# Esquematico.net
KiCad netlist of a schematic drawn in Altium Designer
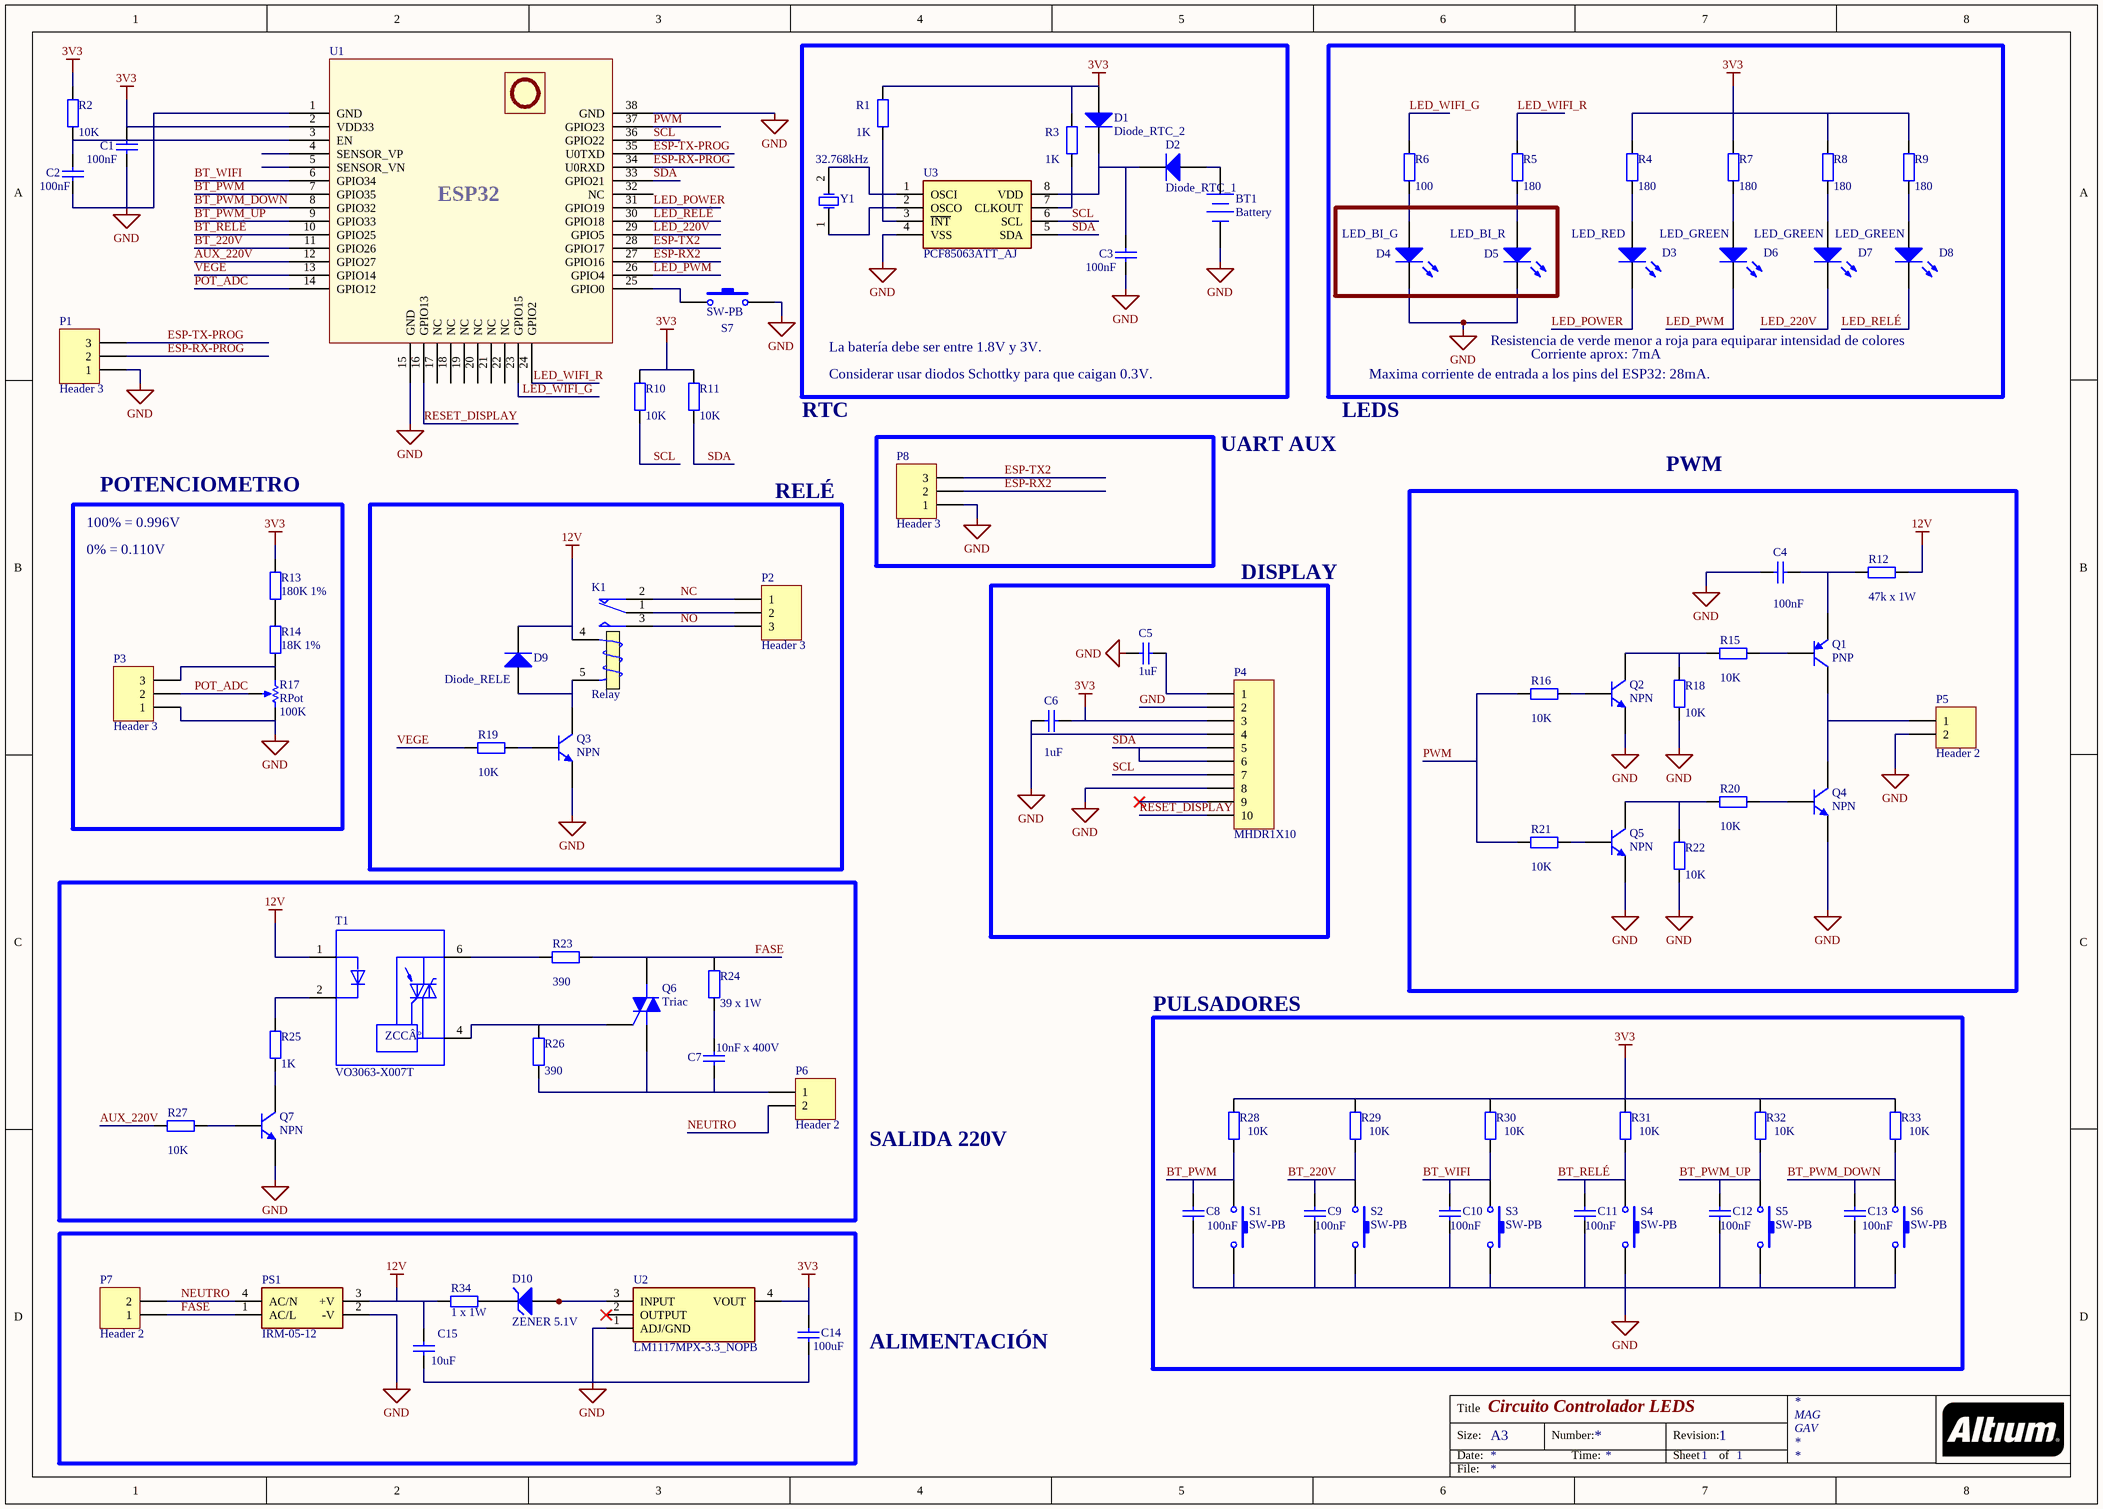
[diagram p0: Esquematico.SchDoc]

(export (version "E")
  (design (tool "Eeschema 10.0.6"))
  (components
    (comp (ref "BT1")
      (value "Battery")
      (footprint "BAT-2")
      (description "Multicell Battery")
      (fields (field (name "PUBLISHER") "Altium Limited"))
      (libsource (lib "Miscellaneous Devices") (part "Battery"))
    )
    (comp (ref "C1")
      (value "100nF")
      (footprint "RAD-0.3")
      (description "Capacitor")
      (fields (field (name "Comment") "Capacitor 100nF") (field (name "PUBLISHER") "Altium Limited"))
      (libsource (lib "Miscellaneous Devices") (part "Cap"))
    )
    (comp (ref "C2")
      (value "100nF")
      (footprint "RAD-0.3")
      (description "Capacitor")
      (fields (field (name "Comment") "Capacitor 100nF") (field (name "PUBLISHER") "Altium Limited"))
      (libsource (lib "Miscellaneous Devices") (part "Cap"))
    )
    (comp (ref "C3")
      (value "100nF")
      (footprint "RAD-0.3")
      (description "Capacitor")
      (fields (field (name "Comment") "Capacitor 100nF") (field (name "PUBLISHER") "Altium Limited"))
      (libsource (lib "Miscellaneous Devices") (part "Cap"))
    )
    (comp (ref "C4")
      (value "100nF")
      (footprint "RAD-0.3")
      (description "Capacitor")
      (fields (field (name "Comment") "Capacitor 100nF") (field (name "PUBLISHER") "Altium Limited"))
      (libsource (lib "Miscellaneous Devices") (part "Cap"))
    )
    (comp (ref "C5")
      (value "1uF")
      (footprint "RAD-0.3")
      (description "Capacitor")
      (fields (field (name "Comment") "Capacitor 1uF") (field (name "PUBLISHER") "Altium Limited"))
      (libsource (lib "Miscellaneous Devices") (part "Cap"))
    )
    (comp (ref "C6")
      (value "1uF")
      (footprint "RAD-0.3")
      (description "Capacitor")
      (fields (field (name "Comment") "Capacitor 1uF") (field (name "PUBLISHER") "Altium Limited"))
      (libsource (lib "Miscellaneous Devices") (part "Cap"))
    )
    (comp (ref "C7")
      (value "10nF x 400V")
      (footprint "RAD-0.3")
      (description "Capacitor")
      (fields (field (name "Comment") "Capacitor 10nF") (field (name "PUBLISHER") "Altium Limited"))
      (libsource (lib "Miscellaneous Devices") (part "Cap"))
    )
    (comp (ref "C8")
      (value "100nF")
      (footprint "RAD-0.3")
      (description "Capacitor")
      (fields (field (name "Comment") "Capacitor 100nF") (field (name "PUBLISHER") "Altium Limited"))
      (libsource (lib "Miscellaneous Devices") (part "Cap"))
    )
    (comp (ref "C9")
      (value "100nF")
      (footprint "RAD-0.3")
      (description "Capacitor")
      (fields (field (name "Comment") "Capacitor 100nF") (field (name "PUBLISHER") "Altium Limited"))
      (libsource (lib "Miscellaneous Devices") (part "Cap"))
    )
    (comp (ref "C10")
      (value "100nF")
      (footprint "RAD-0.3")
      (description "Capacitor")
      (fields (field (name "Comment") "Capacitor 100nF") (field (name "PUBLISHER") "Altium Limited"))
      (libsource (lib "Miscellaneous Devices") (part "Cap"))
    )
    (comp (ref "C11")
      (value "100nF")
      (footprint "RAD-0.3")
      (description "Capacitor")
      (fields (field (name "Comment") "Capacitor 100nF") (field (name "PUBLISHER") "Altium Limited"))
      (libsource (lib "Miscellaneous Devices") (part "Cap"))
    )
    (comp (ref "C12")
      (value "100nF")
      (footprint "RAD-0.3")
      (description "Capacitor")
      (fields (field (name "Comment") "Capacitor 100nF") (field (name "PUBLISHER") "Altium Limited"))
      (libsource (lib "Miscellaneous Devices") (part "Cap"))
    )
    (comp (ref "C13")
      (value "100nF")
      (footprint "RAD-0.3")
      (description "Capacitor")
      (fields (field (name "Comment") "Capacitor 100nF") (field (name "PUBLISHER") "Altium Limited"))
      (libsource (lib "Miscellaneous Devices") (part "Cap"))
    )
    (comp (ref "C14")
      (value "100uF")
      (footprint "RAD-0.3")
      (description "Capacitor")
      (fields (field (name "Comment") "Capacitor 100uF") (field (name "PUBLISHER") "Altium Limited"))
      (libsource (lib "Miscellaneous Devices") (part "Cap"))
    )
    (comp (ref "C15")
      (value "10uF")
      (footprint "RAD-0.3")
      (description "Capacitor")
      (fields (field (name "Comment") "Capacitor 10uF") (field (name "PUBLISHER") "Altium Limited"))
      (libsource (lib "Miscellaneous Devices") (part "Cap"))
    )
    (comp (ref "D1")
      (value "Diode_RTC_2")
      (footprint "SMC")
      (description "Default Diode")
      (fields (field (name "PUBLISHER") "Altium Limited"))
      (libsource (lib "Miscellaneous Devices") (part "Diode"))
    )
    (comp (ref "D2")
      (value "Diode_RTC_1")
      (footprint "SMC")
      (description "Default Diode")
      (fields (field (name "PUBLISHER") "Altium Limited"))
      (libsource (lib "Miscellaneous Devices") (part "Diode"))
    )
    (comp (ref "D3")
      (value "LED_RED")
      (footprint "LED-0")
      (description "Typical INFRARED GaAs LED")
      (fields (field (name "PUBLISHER") "Altium Limited"))
      (libsource (lib "Miscellaneous Devices") (part "LED0"))
    )
    (comp (ref "D4")
      (value "LED_BI_G")
      (footprint "LED-0")
      (description "Typical INFRARED GaAs LED")
      (fields (field (name "PUBLISHER") "Altium Limited"))
      (libsource (lib "Miscellaneous Devices") (part "LED0"))
    )
    (comp (ref "D5")
      (value "LED_BI_R")
      (footprint "LED-0")
      (description "Typical INFRARED GaAs LED")
      (fields (field (name "PUBLISHER") "Altium Limited"))
      (libsource (lib "Miscellaneous Devices") (part "LED0"))
    )
    (comp (ref "D6")
      (value "LED_GREEN")
      (footprint "LED-0")
      (description "Typical INFRARED GaAs LED")
      (fields (field (name "PUBLISHER") "Altium Limited"))
      (libsource (lib "Miscellaneous Devices") (part "LED0"))
    )
    (comp (ref "D7")
      (value "LED_GREEN")
      (footprint "LED-0")
      (description "Typical INFRARED GaAs LED")
      (fields (field (name "PUBLISHER") "Altium Limited"))
      (libsource (lib "Miscellaneous Devices") (part "LED0"))
    )
    (comp (ref "D8")
      (value "LED_GREEN")
      (footprint "LED-0")
      (description "Typical INFRARED GaAs LED")
      (fields (field (name "PUBLISHER") "Altium Limited"))
      (libsource (lib "Miscellaneous Devices") (part "LED0"))
    )
    (comp (ref "D9")
      (value "Diode_RELE")
      (footprint "SMC")
      (description "Default Diode")
      (fields (field (name "PUBLISHER") "Altium Limited"))
      (libsource (lib "Miscellaneous Devices") (part "Diode"))
    )
    (comp (ref "D10")
      (value "ZENER 5.1V")
      (footprint "DIODE-0.7")
      (description "Zener Diode")
      (fields (field (name "PUBLISHER") "Altium Limited"))
      (libsource (lib "Miscellaneous Devices") (part "D Zener"))
    )
    (comp (ref "K1")
      (value "Relay")
      (footprint "MODULE5B")
      (description "SPDT Relay")
      (fields (field (name "PUBLISHER") "Altium Limited"))
      (libsource (lib "Miscellaneous Devices") (part "Relay"))
    )
    (comp (ref "P1")
      (value "Header 3")
      (footprint "HDR1X3")
      (description "Header, 3-Pin")
      (fields (field (name "PUBLISHER") "Altium Limited"))
      (libsource (lib "Miscellaneous Connectors") (part "Header 3"))
    )
    (comp (ref "P2")
      (value "Header 3")
      (footprint "HDR1X3")
      (description "Header, 3-Pin")
      (fields (field (name "PUBLISHER") "Altium Limited"))
      (libsource (lib "") (part "Header 3_1"))
    )
    (comp (ref "P3")
      (value "Header 3")
      (footprint "HDR1X3")
      (description "Header, 3-Pin")
      (fields (field (name "PUBLISHER") "Altium Limited"))
      (libsource (lib "Miscellaneous Connectors") (part "Header 3"))
    )
    (comp (ref "P4")
      (value "MHDR1X10")
      (footprint "MHDR1X10")
      (description "Header, 10-Pin")
      (fields (field (name "PUBLISHER") "Altium Limited"))
      (libsource (lib "Miscellaneous Connectors") (part "MHDR1X10"))
    )
    (comp (ref "P5")
      (value "Header 2")
      (footprint "HDR1X2")
      (description "Header, 2-Pin")
      (fields (field (name "PUBLISHER") "Altium Limited"))
      (libsource (lib "Miscellaneous Connectors") (part "Header 2"))
    )
    (comp (ref "P6")
      (value "Header 2")
      (footprint "HDR1X2")
      (description "Header, 2-Pin")
      (fields (field (name "PUBLISHER") "Altium Limited"))
      (libsource (lib "Miscellaneous Connectors") (part "Header 2"))
    )
    (comp (ref "P7")
      (value "Header 2")
      (footprint "HDR1X2")
      (description "Header, 2-Pin")
      (fields (field (name "PUBLISHER") "Altium Limited"))
      (libsource (lib "") (part "Header 2_1"))
    )
    (comp (ref "P8")
      (value "Header 3")
      (footprint "HDR1X3")
      (description "Header, 3-Pin")
      (fields (field (name "PUBLISHER") "Altium Limited"))
      (libsource (lib "Miscellaneous Connectors") (part "Header 3"))
    )
    (comp (ref "PS1")
      (value "IRM-05-12")
      (footprint "SamacSys:IRM0524")
      (description "Power Supply")
      (fields
        (field (name "MANUFACTURER_PART_NUMBER") "IRM-05-24")
        (field (name "MOUSER PART NUMBER") "709-IRM05-24")
      )
      (libsource (lib "*") (part "IRM-05-24"))
    )
    (comp (ref "Q1")
      (value "PNP")
      (footprint "SOT-23B_L")
      (description "PNP Bipolar Transistor")
      (fields (field (name "PUBLISHER") "Altium Limited"))
      (libsource (lib "Miscellaneous Devices") (part "PNP"))
    )
    (comp (ref "Q2")
      (value "NPN")
      (footprint "TO-226-AA")
      (description "NPN Bipolar Transistor")
      (fields (field (name "PUBLISHER") "Altium Limited"))
      (libsource (lib "Miscellaneous Devices") (part "NPN"))
    )
    (comp (ref "Q3")
      (value "NPN")
      (footprint "TO-226-AA")
      (description "NPN Bipolar Transistor")
      (fields (field (name "PUBLISHER") "Altium Limited"))
      (libsource (lib "Miscellaneous Devices") (part "NPN"))
    )
    (comp (ref "Q4")
      (value "NPN")
      (footprint "TO-226-AA")
      (description "NPN Bipolar Transistor")
      (fields (field (name "PUBLISHER") "Altium Limited"))
      (libsource (lib "Miscellaneous Devices") (part "NPN"))
    )
    (comp (ref "Q5")
      (value "NPN")
      (footprint "TO-226-AA")
      (description "NPN Bipolar Transistor")
      (fields (field (name "PUBLISHER") "Altium Limited"))
      (libsource (lib "Miscellaneous Devices") (part "NPN"))
    )
    (comp (ref "Q6")
      (value "Triac")
      (footprint "369-03")
      (description "Silicon Bidirectional Triode Thyristor")
      (fields (field (name "PUBLISHER") "Altium Limited"))
      (libsource (lib "Miscellaneous Devices") (part "Triac"))
    )
    (comp (ref "Q7")
      (value "NPN")
      (footprint "TO-226-AA")
      (description "NPN Bipolar Transistor")
      (fields (field (name "PUBLISHER") "Altium Limited"))
      (libsource (lib "Miscellaneous Devices") (part "NPN"))
    )
    (comp (ref "R1")
      (value "1K")
      (footprint "AXIAL-0.4")
      (description "Resistor")
      (fields (field (name "Comment") "Resistor 1k") (field (name "PUBLISHER") "Altium Limited"))
      (libsource (lib "") (part "Res2_1"))
    )
    (comp (ref "R2")
      (value "10K")
      (footprint "AXIAL-0.4")
      (description "Resistor")
      (fields (field (name "Comment") "Resistor 10k") (field (name "PUBLISHER") "Altium Limited"))
      (libsource (lib "Miscellaneous Devices") (part "Res2"))
    )
    (comp (ref "R3")
      (value "1K")
      (footprint "AXIAL-0.4")
      (description "Resistor")
      (fields (field (name "Comment") "Resistor 1k") (field (name "PUBLISHER") "Altium Limited"))
      (libsource (lib "") (part "Res2_1"))
    )
    (comp (ref "R4")
      (value "180")
      (footprint "AXIAL-0.4")
      (description "Resistor")
      (fields (field (name "Comment") "Resistor 100") (field (name "PUBLISHER") "Altium Limited"))
      (libsource (lib "") (part "Res2_1"))
    )
    (comp (ref "R5")
      (value "180")
      (footprint "AXIAL-0.4")
      (description "Resistor")
      (fields (field (name "Comment") "Resistor 50") (field (name "PUBLISHER") "Altium Limited"))
      (libsource (lib "") (part "Res2_1"))
    )
    (comp (ref "R6")
      (value "100")
      (footprint "AXIAL-0.4")
      (description "Resistor")
      (fields (field (name "Comment") "Resistor 100") (field (name "PUBLISHER") "Altium Limited"))
      (libsource (lib "") (part "Res2_1"))
    )
    (comp (ref "R7")
      (value "180")
      (footprint "AXIAL-0.4")
      (description "Resistor")
      (fields (field (name "Comment") "Resistor 100") (field (name "PUBLISHER") "Altium Limited"))
      (libsource (lib "") (part "Res2_1"))
    )
    (comp (ref "R8")
      (value "180")
      (footprint "AXIAL-0.4")
      (description "Resistor")
      (fields (field (name "Comment") "Resistor 100") (field (name "PUBLISHER") "Altium Limited"))
      (libsource (lib "") (part "Res2_1"))
    )
    (comp (ref "R9")
      (value "180")
      (footprint "AXIAL-0.4")
      (description "Resistor")
      (fields (field (name "Comment") "Resistor 100") (field (name "PUBLISHER") "Altium Limited"))
      (libsource (lib "") (part "Res2_1"))
    )
    (comp (ref "R10")
      (value "10K")
      (footprint "AXIAL-0.4")
      (description "Resistor")
      (fields (field (name "Comment") "Resistor 10k") (field (name "PUBLISHER") "Altium Limited"))
      (libsource (lib "Miscellaneous Devices") (part "Res2"))
    )
    (comp (ref "R11")
      (value "10K")
      (footprint "AXIAL-0.4")
      (description "Resistor")
      (fields (field (name "Comment") "Resistor 10k") (field (name "PUBLISHER") "Altium Limited"))
      (libsource (lib "Miscellaneous Devices") (part "Res2"))
    )
    (comp (ref "R12")
      (value "47k x 1W")
      (footprint "AXIAL-0.4")
      (description "Resistor")
      (fields (field (name "Comment") "Resistor 47k") (field (name "PUBLISHER") "Altium Limited"))
      (libsource (lib "") (part "Res2_2"))
    )
    (comp (ref "R13")
      (value "180K 1%")
      (footprint "AXIAL-0.4")
      (description "Resistor")
      (fields (field (name "Comment") "Resistor 180k") (field (name "PUBLISHER") "Altium Limited"))
      (libsource (lib "Miscellaneous Devices") (part "Res2"))
    )
    (comp (ref "R14")
      (value "18K 1%")
      (footprint "AXIAL-0.4")
      (description "Resistor")
      (fields (field (name "Comment") "Resistor 18k 1%") (field (name "PUBLISHER") "Altium Limited"))
      (libsource (lib "Miscellaneous Devices") (part "Res2"))
    )
    (comp (ref "R15")
      (value "10K")
      (footprint "AXIAL-0.4")
      (description "Resistor")
      (fields (field (name "Comment") "Resistor 10k") (field (name "PUBLISHER") "Altium Limited"))
      (libsource (lib "") (part "Res2_2"))
    )
    (comp (ref "R16")
      (value "10K")
      (footprint "AXIAL-0.4")
      (description "Resistor")
      (fields (field (name "Comment") "Resistor 10k") (field (name "PUBLISHER") "Altium Limited"))
      (libsource (lib "") (part "Res2_2"))
    )
    (comp (ref "R17")
      (value "RPot")
      (footprint "VR5")
      (description "Potentiometer")
      (fields (field (name "ALTIUM_VALUE") "100K") (field (name "PUBLISHER") "Altium Limited"))
      (libsource (lib "Miscellaneous Devices") (part "RPot"))
    )
    (comp (ref "R18")
      (value "10K")
      (footprint "AXIAL-0.4")
      (description "Resistor")
      (fields (field (name "Comment") "Resistor 10k") (field (name "PUBLISHER") "Altium Limited"))
      (libsource (lib "") (part "Res2_1"))
    )
    (comp (ref "R19")
      (value "10K")
      (footprint "AXIAL-0.4")
      (description "Resistor")
      (fields (field (name "Comment") "Resistor 10k") (field (name "PUBLISHER") "Altium Limited"))
      (libsource (lib "") (part "Res2_3"))
    )
    (comp (ref "R20")
      (value "10K")
      (footprint "AXIAL-0.4")
      (description "Resistor")
      (fields (field (name "Comment") "Resistor 10k") (field (name "PUBLISHER") "Altium Limited"))
      (libsource (lib "") (part "Res2_2"))
    )
    (comp (ref "R21")
      (value "10K")
      (footprint "AXIAL-0.4")
      (description "Resistor")
      (fields (field (name "Comment") "Resistor 10k") (field (name "PUBLISHER") "Altium Limited"))
      (libsource (lib "") (part "Res2_2"))
    )
    (comp (ref "R22")
      (value "10K")
      (footprint "AXIAL-0.4")
      (description "Resistor")
      (fields (field (name "Comment") "Resistor 10k") (field (name "PUBLISHER") "Altium Limited"))
      (libsource (lib "") (part "Res2_1"))
    )
    (comp (ref "R23")
      (value "390")
      (footprint "AXIAL-0.4")
      (description "Resistor")
      (fields (field (name "Comment") "Resistor 390") (field (name "PUBLISHER") "Altium Limited"))
      (libsource (lib "") (part "Res2_3"))
    )
    (comp (ref "R24")
      (value "39 x 1W")
      (footprint "AXIAL-0.4")
      (description "Resistor")
      (fields (field (name "Comment") "Resistor 39") (field (name "PUBLISHER") "Altium Limited"))
      (libsource (lib "") (part "Res2_1"))
    )
    (comp (ref "R25")
      (value "1K")
      (footprint "AXIAL-0.4")
      (description "Resistor")
      (fields (field (name "Comment") "Resistor 1k") (field (name "PUBLISHER") "Altium Limited"))
      (libsource (lib "") (part "Res2_1"))
    )
    (comp (ref "R26")
      (value "390")
      (footprint "AXIAL-0.4")
      (description "Resistor")
      (fields (field (name "Comment") "Resistor 390") (field (name "PUBLISHER") "Altium Limited"))
      (libsource (lib "Miscellaneous Devices") (part "Res2"))
    )
    (comp (ref "R27")
      (value "10K")
      (footprint "AXIAL-0.4")
      (description "Resistor")
      (fields (field (name "Comment") "Resistor 10k") (field (name "PUBLISHER") "Altium Limited"))
      (libsource (lib "") (part "Res2_3"))
    )
    (comp (ref "R28")
      (value "10K")
      (footprint "AXIAL-0.4")
      (description "Resistor")
      (fields (field (name "Comment") "Resistor 10k") (field (name "PUBLISHER") "Altium Limited"))
      (libsource (lib "") (part "Res2_1"))
    )
    (comp (ref "R29")
      (value "10K")
      (footprint "AXIAL-0.4")
      (description "Resistor")
      (fields (field (name "Comment") "Resistor 10k") (field (name "PUBLISHER") "Altium Limited"))
      (libsource (lib "") (part "Res2_1"))
    )
    (comp (ref "R30")
      (value "10K")
      (footprint "AXIAL-0.4")
      (description "Resistor")
      (fields (field (name "Comment") "Resistor 10k") (field (name "PUBLISHER") "Altium Limited"))
      (libsource (lib "") (part "Res2_1"))
    )
    (comp (ref "R31")
      (value "10K")
      (footprint "AXIAL-0.4")
      (description "Resistor")
      (fields (field (name "Comment") "Resistor 10k") (field (name "PUBLISHER") "Altium Limited"))
      (libsource (lib "") (part "Res2_1"))
    )
    (comp (ref "R32")
      (value "10K")
      (footprint "AXIAL-0.4")
      (description "Resistor")
      (fields (field (name "Comment") "Resistor 10k") (field (name "PUBLISHER") "Altium Limited"))
      (libsource (lib "") (part "Res2_1"))
    )
    (comp (ref "R33")
      (value "10K")
      (footprint "AXIAL-0.4")
      (description "Resistor")
      (fields (field (name "Comment") "Resistor 10k") (field (name "PUBLISHER") "Altium Limited"))
      (libsource (lib "") (part "Res2_1"))
    )
    (comp (ref "R34")
      (value "1 x 1W")
      (footprint "AXIAL-0.4")
      (description "Resistor")
      (fields (field (name "Comment") "Resistor 1") (field (name "PUBLISHER") "Altium Limited"))
      (libsource (lib "") (part "Res2_2"))
    )
    (comp (ref "S1")
      (value "SW-PB")
      (footprint "SPST-2")
      (description "Switch")
      (fields (field (name "PUBLISHER") "Altium Limited"))
      (libsource (lib "Miscellaneous Devices") (part "SW-PB"))
    )
    (comp (ref "S2")
      (value "SW-PB")
      (footprint "SPST-2")
      (description "Switch")
      (fields (field (name "PUBLISHER") "Altium Limited"))
      (libsource (lib "Miscellaneous Devices") (part "SW-PB"))
    )
    (comp (ref "S3")
      (value "SW-PB")
      (footprint "SPST-2")
      (description "Switch")
      (fields (field (name "PUBLISHER") "Altium Limited"))
      (libsource (lib "Miscellaneous Devices") (part "SW-PB"))
    )
    (comp (ref "S4")
      (value "SW-PB")
      (footprint "SPST-2")
      (description "Switch")
      (fields (field (name "PUBLISHER") "Altium Limited"))
      (libsource (lib "Miscellaneous Devices") (part "SW-PB"))
    )
    (comp (ref "S5")
      (value "SW-PB")
      (footprint "SPST-2")
      (description "Switch")
      (fields (field (name "PUBLISHER") "Altium Limited"))
      (libsource (lib "Miscellaneous Devices") (part "SW-PB"))
    )
    (comp (ref "S6")
      (value "SW-PB")
      (footprint "SPST-2")
      (description "Switch")
      (fields (field (name "PUBLISHER") "Altium Limited"))
      (libsource (lib "Miscellaneous Devices") (part "SW-PB"))
    )
    (comp (ref "S7")
      (value "SW-PB")
      (footprint "SPST-2")
      (description "Switch")
      (fields (field (name "PUBLISHER") "Altium Limited"))
      (libsource (lib "Miscellaneous Devices") (part "SW-PB"))
    )
    (comp (ref "T1")
      (value "VO3063-X007T")
      (footprint "SOIC254P1030X460-6N")
      (description "Phototriac, Zero Crossing, 1.5 kV/渭s dV/dt, 600 V")
      (libsource (lib "VO3063-X007T") (part "VO3063-X007T"))
    )
    (comp (ref "U1") (value "ESP32-WROOM-UE32") (libsource (lib "ESP32-WROOM-32UE") (part "Component_1")))
    (comp (ref "U2")
      (value "LM1117MPX-3.3_NOPB")
      (footprint "SamacSys:SOT230P700X180-4N")
      (description "Integrated Circuit")
      (fields
        (field (name "MANUFACTURER_PART_NUMBER") "LM1117MPX-3.3/NOPB")
        (field (name "MOUSER PART NUMBER") "926-LM1117MPX3.3NOPB")
      )
      (libsource (lib "SamacSys") (part "LM1117MPX-3.3_NOPB"))
    )
    (comp (ref "U3")
      (value "PCF85063ATT_AJ")
      (footprint "SamacSys:SOP65P490X110-8N")
      (description "Integrated Circuit")
      (fields
        (field (name "MANUFACTURER_PART_NUMBER") "PCF85063ATT/AJ")
        (field (name "MOUSER PART NUMBER") "771-PCF85063ATT/AJ")
      )
      (libsource (lib "*") (part "PCF85063ATT_AJ"))
    )
    (comp (ref "Y1")
      (value "32.768kHz")
      (footprint "R38")
      (description "Crystal Oscillator")
      (fields (field (name "PUBLISHER") "Altium Limited"))
      (libsource (lib "Miscellaneous Devices") (part "XTAL"))
    )
  )
  (nets
    (net (code "1") (name "/AUX_220V") (class "Default")
      (node (ref "R27") (pin "2") (pinfunction "2_2") (pintype "passive"))
      (node (ref "U1") (pin "12") (pinfunction "GPIO27_12") (pintype "passive"))
    )
    (net (code "2") (name "/BT_220V") (class "Default")
      (node (ref "C9") (pin "2") (pinfunction "2_2") (pintype "passive"))
      (node (ref "R29") (pin "1") (pinfunction "1_1") (pintype "passive"))
      (node (ref "S2") (pin "1") (pinfunction "1_1") (pintype "passive"))
      (node (ref "U1") (pin "11") (pinfunction "GPIO26_11") (pintype "passive"))
    )
    (net (code "3") (name "/BT_PWM") (class "Default")
      (node (ref "C8") (pin "2") (pinfunction "2_2") (pintype "passive"))
      (node (ref "R28") (pin "1") (pinfunction "1_1") (pintype "passive"))
      (node (ref "S1") (pin "1") (pinfunction "1_1") (pintype "passive"))
      (node (ref "U1") (pin "7") (pinfunction "GPIO35_7") (pintype "passive"))
    )
    (net (code "4") (name "/BT_PWM_DOWN") (class "Default")
      (node (ref "C13") (pin "2") (pinfunction "2_2") (pintype "passive"))
      (node (ref "R33") (pin "1") (pinfunction "1_1") (pintype "passive"))
      (node (ref "S6") (pin "1") (pinfunction "1_1") (pintype "passive"))
      (node (ref "U1") (pin "8") (pinfunction "GPIO32_8") (pintype "passive"))
    )
    (net (code "5") (name "/BT_PWM_UP") (class "Default")
      (node (ref "C12") (pin "2") (pinfunction "2_2") (pintype "passive"))
      (node (ref "R32") (pin "1") (pinfunction "1_1") (pintype "passive"))
      (node (ref "S5") (pin "1") (pinfunction "1_1") (pintype "passive"))
      (node (ref "U1") (pin "9") (pinfunction "GPIO33_9") (pintype "passive"))
    )
    (net (code "6") (name "/BT_RELÉ") (class "Default")
      (node (ref "C11") (pin "2") (pinfunction "2_2") (pintype "passive"))
      (node (ref "R31") (pin "1") (pinfunction "1_1") (pintype "passive"))
      (node (ref "S4") (pin "1") (pinfunction "1_1") (pintype "passive"))
      (node (ref "U1") (pin "10") (pinfunction "GPIO25_10") (pintype "passive"))
    )
    (net (code "7") (name "/BT_WIFI") (class "Default")
      (node (ref "C10") (pin "2") (pinfunction "2_2") (pintype "passive"))
      (node (ref "R30") (pin "1") (pinfunction "1_1") (pintype "passive"))
      (node (ref "S3") (pin "1") (pinfunction "1_1") (pintype "passive"))
      (node (ref "U1") (pin "6") (pinfunction "GPIO34_6") (pintype "passive"))
    )
    (net (code "8") (name "/ESP-RX-PROG") (class "Default")
      (node (ref "P1") (pin "2") (pinfunction "2_2") (pintype "passive"))
      (node (ref "U1") (pin "34") (pinfunction "U0RXD_34") (pintype "passive"))
    )
    (net (code "9") (name "/ESP-RX2") (class "Default")
      (node (ref "P8") (pin "2") (pinfunction "2_2") (pintype "passive"))
      (node (ref "U1") (pin "27") (pinfunction "GPIO16_27") (pintype "passive"))
    )
    (net (code "10") (name "/ESP-TX-PROG") (class "Default")
      (node (ref "P1") (pin "3") (pinfunction "3_3") (pintype "passive"))
      (node (ref "U1") (pin "35") (pinfunction "U0TXD_35") (pintype "passive"))
    )
    (net (code "11") (name "/ESP-TX2") (class "Default")
      (node (ref "P8") (pin "3") (pinfunction "3_3") (pintype "passive"))
      (node (ref "U1") (pin "28") (pinfunction "GPIO17_28") (pintype "passive"))
    )
    (net (code "12") (name "/FASE") (class "Default")
      (node (ref "P7") (pin "1") (pinfunction "1_1") (pintype "passive"))
      (node (ref "PS1") (pin "1") (pinfunction "AC/L_1") (pintype "passive"))
      (node (ref "Q6") (pin "2") (pinfunction "M2_2") (pintype "passive"))
      (node (ref "R23") (pin "1") (pinfunction "1_1") (pintype "passive"))
      (node (ref "R24") (pin "2") (pinfunction "2_2") (pintype "passive"))
    )
    (net (code "13") (name "/LED_220V") (class "Default")
      (node (ref "D7") (pin "2") (pinfunction "K_2") (pintype "passive"))
      (node (ref "U1") (pin "29") (pinfunction "GPIO5_29") (pintype "passive"))
    )
    (net (code "14") (name "/LED_POWER") (class "Default")
      (node (ref "D3") (pin "2") (pinfunction "K_2") (pintype "passive"))
      (node (ref "U1") (pin "31") (pinfunction "GPIO19_31") (pintype "passive"))
    )
    (net (code "15") (name "/LED_PWM") (class "Default")
      (node (ref "D6") (pin "2") (pinfunction "K_2") (pintype "passive"))
      (node (ref "U1") (pin "26") (pinfunction "GPIO4_26") (pintype "passive"))
    )
    (net (code "16") (name "/LED_RELÉ") (class "Default")
      (node (ref "D8") (pin "2") (pinfunction "K_2") (pintype "passive"))
      (node (ref "U1") (pin "30") (pinfunction "GPIO18_30") (pintype "passive"))
    )
    (net (code "17") (name "/LED_WIFI_G") (class "Default")
      (node (ref "R6") (pin "2") (pinfunction "2_2") (pintype "passive"))
      (node (ref "U1") (pin "23") (pinfunction "GPIO15_23") (pintype "passive"))
    )
    (net (code "18") (name "/LED_WIFI_R") (class "Default")
      (node (ref "R5") (pin "2") (pinfunction "2_2") (pintype "passive"))
      (node (ref "U1") (pin "24") (pinfunction "GPIO2_24") (pintype "passive"))
    )
    (net (code "19") (name "/NC") (class "Default")
      (node (ref "K1") (pin "2") (pinfunction "NC_2") (pintype "passive"))
      (node (ref "P2") (pin "1") (pinfunction "1_1") (pintype "passive"))
    )
    (net (code "20") (name "/NEUTRO") (class "Default")
      (node (ref "P6") (pin "2") (pinfunction "2_2") (pintype "passive"))
      (node (ref "P7") (pin "2") (pinfunction "2_2") (pintype "passive"))
      (node (ref "PS1") (pin "4") (pinfunction "AC/N_4") (pintype "passive"))
    )
    (net (code "21") (name "/NO") (class "Default")
      (node (ref "K1") (pin "3") (pinfunction "NO_3") (pintype "passive"))
      (node (ref "P2") (pin "3") (pinfunction "3_3") (pintype "passive"))
    )
    (net (code "22") (name "/POT_ADC") (class "Default")
      (node (ref "P3") (pin "2") (pinfunction "2_2") (pintype "passive"))
      (node (ref "R17") (pin "3") (pinfunction "TAP_3") (pintype "passive"))
      (node (ref "U1") (pin "14") (pinfunction "GPIO12_14") (pintype "passive"))
    )
    (net (code "23") (name "/PWM") (class "Default")
      (node (ref "R16") (pin "1") (pinfunction "1_1") (pintype "passive"))
      (node (ref "R21") (pin "1") (pinfunction "1_1") (pintype "passive"))
      (node (ref "U1") (pin "37") (pinfunction "GPIO23_37") (pintype "passive"))
    )
    (net (code "24") (name "/RESET_DISPLAY") (class "Default")
      (node (ref "P4") (pin "10") (pinfunction "10_10") (pintype "passive"))
      (node (ref "U1") (pin "16") (pinfunction "GPIO13_16") (pintype "passive"))
    )
    (net (code "25") (name "/SCL") (class "Default")
      (node (ref "P4") (pin "7") (pinfunction "7_7") (pintype "passive"))
      (node (ref "R10") (pin "2") (pinfunction "2_2") (pintype "passive"))
      (node (ref "U1") (pin "36") (pinfunction "GPIO22_36") (pintype "passive"))
      (node (ref "U3") (pin "6") (pinfunction "SCL_6") (pintype "passive"))
    )
    (net (code "26") (name "/SDA") (class "Default")
      (node (ref "P4") (pin "5") (pinfunction "5_5") (pintype "passive"))
      (node (ref "P4") (pin "6") (pinfunction "6_6") (pintype "passive"))
      (node (ref "R11") (pin "2") (pinfunction "2_2") (pintype "passive"))
      (node (ref "U1") (pin "33") (pinfunction "GPIO21_33") (pintype "passive"))
      (node (ref "U3") (pin "5") (pinfunction "SDA_5") (pintype "passive"))
    )
    (net (code "27") (name "/VEGE") (class "Default")
      (node (ref "R19") (pin "2") (pinfunction "2_2") (pintype "passive"))
      (node (ref "U1") (pin "13") (pinfunction "GPIO14_13") (pintype "passive"))
    )
    (net (code "28") (name "3V3") (class "Default")
      (node (ref "C1") (pin "2") (pinfunction "2_2") (pintype "passive"))
      (node (ref "C14") (pin "2") (pinfunction "2_2") (pintype "passive"))
      (node (ref "C6") (pin "1") (pinfunction "1_1") (pintype "passive"))
      (node (ref "D1") (pin "1") (pinfunction "A_1") (pintype "passive"))
      (node (ref "P4") (pin "3") (pinfunction "3_3") (pintype "passive"))
      (node (ref "R1") (pin "2") (pinfunction "2_2") (pintype "passive"))
      (node (ref "R10") (pin "1") (pinfunction "1_1") (pintype "passive"))
      (node (ref "R11") (pin "1") (pinfunction "1_1") (pintype "passive"))
      (node (ref "R13") (pin "1") (pinfunction "1_1") (pintype "passive"))
      (node (ref "R2") (pin "1") (pinfunction "1_1") (pintype "passive"))
      (node (ref "R28") (pin "2") (pinfunction "2_2") (pintype "passive"))
      (node (ref "R29") (pin "2") (pinfunction "2_2") (pintype "passive"))
      (node (ref "R3") (pin "2") (pinfunction "2_2") (pintype "passive"))
      (node (ref "R30") (pin "2") (pinfunction "2_2") (pintype "passive"))
      (node (ref "R31") (pin "2") (pinfunction "2_2") (pintype "passive"))
      (node (ref "R32") (pin "2") (pinfunction "2_2") (pintype "passive"))
      (node (ref "R33") (pin "2") (pinfunction "2_2") (pintype "passive"))
      (node (ref "R4") (pin "2") (pinfunction "2_2") (pintype "passive"))
      (node (ref "R7") (pin "2") (pinfunction "2_2") (pintype "passive"))
      (node (ref "R8") (pin "2") (pinfunction "2_2") (pintype "passive"))
      (node (ref "R9") (pin "2") (pinfunction "2_2") (pintype "passive"))
      (node (ref "U1") (pin "2") (pinfunction "VDD33_2") (pintype "passive"))
      (node (ref "U2") (pin "4") (pinfunction "VOUT_4") (pintype "passive"))
    )
    (net (code "29") (name "12V") (class "Default")
      (node (ref "C15") (pin "2") (pinfunction "2_2") (pintype "passive"))
      (node (ref "D9") (pin "2") (pinfunction "K_2") (pintype "passive"))
      (node (ref "K1") (pin "4") (pinfunction "T1_4") (pintype "passive"))
      (node (ref "PS1") (pin "3") (pinfunction "+V_3") (pintype "passive"))
      (node (ref "R12") (pin "2") (pinfunction "2_2") (pintype "passive"))
      (node (ref "R34") (pin "1") (pinfunction "1_1") (pintype "passive"))
      (node (ref "T1") (pin "1") (pinfunction "A_1") (pintype "passive"))
    )
    (net (code "30") (name "GND") (class "Default")
      (node (ref "BT1") (pin "2") (pinfunction "-_2") (pintype "passive"))
      (node (ref "C1") (pin "1") (pinfunction "1_1") (pintype "passive"))
      (node (ref "C10") (pin "1") (pinfunction "1_1") (pintype "passive"))
      (node (ref "C11") (pin "1") (pinfunction "1_1") (pintype "passive"))
      (node (ref "C12") (pin "1") (pinfunction "1_1") (pintype "passive"))
      (node (ref "C13") (pin "1") (pinfunction "1_1") (pintype "passive"))
      (node (ref "C14") (pin "1") (pinfunction "1_1") (pintype "passive"))
      (node (ref "C15") (pin "1") (pinfunction "1_1") (pintype "passive"))
      (node (ref "C2") (pin "1") (pinfunction "1_1") (pintype "passive"))
      (node (ref "C3") (pin "1") (pinfunction "1_1") (pintype "passive"))
      (node (ref "C4") (pin "1") (pinfunction "1_1") (pintype "passive"))
      (node (ref "C5") (pin "2") (pinfunction "2_2") (pintype "passive"))
      (node (ref "C6") (pin "2") (pinfunction "2_2") (pintype "passive"))
      (node (ref "C8") (pin "1") (pinfunction "1_1") (pintype "passive"))
      (node (ref "C9") (pin "1") (pinfunction "1_1") (pintype "passive"))
      (node (ref "D4") (pin "2") (pinfunction "K_2") (pintype "passive"))
      (node (ref "D5") (pin "2") (pinfunction "K_2") (pintype "passive"))
      (node (ref "P1") (pin "1") (pinfunction "1_1") (pintype "passive"))
      (node (ref "P3") (pin "1") (pinfunction "1_1") (pintype "passive"))
      (node (ref "P4") (pin "2") (pinfunction "2_2") (pintype "passive"))
      (node (ref "P4") (pin "4") (pinfunction "4_4") (pintype "passive"))
      (node (ref "P4") (pin "8") (pinfunction "8_8") (pintype "passive"))
      (node (ref "P5") (pin "2") (pinfunction "2_2") (pintype "passive"))
      (node (ref "P8") (pin "1") (pinfunction "1_1") (pintype "passive"))
      (node (ref "PS1") (pin "2") (pinfunction "-V_2") (pintype "passive"))
      (node (ref "Q2") (pin "3") (pinfunction "E_3") (pintype "passive"))
      (node (ref "Q3") (pin "3") (pinfunction "E_3") (pintype "passive"))
      (node (ref "Q4") (pin "3") (pinfunction "E_3") (pintype "passive"))
      (node (ref "Q5") (pin "3") (pinfunction "E_3") (pintype "passive"))
      (node (ref "Q7") (pin "3") (pinfunction "E_3") (pintype "passive"))
      (node (ref "R17") (pin "2") (pinfunction "BOT_2") (pintype "passive"))
      (node (ref "R18") (pin "1") (pinfunction "1_1") (pintype "passive"))
      (node (ref "R22") (pin "1") (pinfunction "1_1") (pintype "passive"))
      (node (ref "S1") (pin "2") (pinfunction "2_2") (pintype "passive"))
      (node (ref "S2") (pin "2") (pinfunction "2_2") (pintype "passive"))
      (node (ref "S3") (pin "2") (pinfunction "2_2") (pintype "passive"))
      (node (ref "S4") (pin "2") (pinfunction "2_2") (pintype "passive"))
      (node (ref "S5") (pin "2") (pinfunction "2_2") (pintype "passive"))
      (node (ref "S6") (pin "2") (pinfunction "2_2") (pintype "passive"))
      (node (ref "S7") (pin "2") (pinfunction "2_2") (pintype "passive"))
      (node (ref "U1") (pin "1") (pinfunction "GND_1") (pintype "passive"))
      (node (ref "U1") (pin "15") (pinfunction "GND_15") (pintype "passive"))
      (node (ref "U1") (pin "38") (pinfunction "GND_38") (pintype "passive"))
      (node (ref "U2") (pin "1") (pinfunction "ADJ/GND_1") (pintype "passive"))
      (node (ref "U3") (pin "4") (pinfunction "VSS_4") (pintype "passive"))
    )
    (net (code "31") (name "Net-(BT1-+)") (class "Default")
      (node (ref "BT1") (pin "1") (pinfunction "+_1") (pintype "passive"))
      (node (ref "D2") (pin "1") (pinfunction "A_1") (pintype "passive"))
    )
    (net (code "32") (name "Net-(C5-Pad1)") (class "Default")
      (node (ref "C5") (pin "1") (pinfunction "1_1") (pintype "passive"))
      (node (ref "P4") (pin "1") (pinfunction "1_1") (pintype "passive"))
    )
    (net (code "33") (name "Net-(C7-Pad2)") (class "Default")
      (node (ref "C7") (pin "2") (pinfunction "2_2") (pintype "passive"))
      (node (ref "R24") (pin "1") (pinfunction "1_1") (pintype "passive"))
    )
    (net (code "34") (name "Net-(D1-K)") (class "Default")
      (node (ref "C3") (pin "2") (pinfunction "2_2") (pintype "passive"))
      (node (ref "D1") (pin "2") (pinfunction "K_2") (pintype "passive"))
      (node (ref "D2") (pin "2") (pinfunction "K_2") (pintype "passive"))
      (node (ref "U3") (pin "8") (pinfunction "VDD_8") (pintype "passive"))
    )
    (net (code "35") (name "Net-(D3-A)") (class "Default")
      (node (ref "D3") (pin "1") (pinfunction "A_1") (pintype "passive"))
      (node (ref "R4") (pin "1") (pinfunction "1_1") (pintype "passive"))
    )
    (net (code "36") (name "Net-(D4-A)") (class "Default")
      (node (ref "D4") (pin "1") (pinfunction "A_1") (pintype "passive"))
      (node (ref "R6") (pin "1") (pinfunction "1_1") (pintype "passive"))
    )
    (net (code "37") (name "Net-(D5-A)") (class "Default")
      (node (ref "D5") (pin "1") (pinfunction "A_1") (pintype "passive"))
      (node (ref "R5") (pin "1") (pinfunction "1_1") (pintype "passive"))
    )
    (net (code "38") (name "Net-(D6-A)") (class "Default")
      (node (ref "D6") (pin "1") (pinfunction "A_1") (pintype "passive"))
      (node (ref "R7") (pin "1") (pinfunction "1_1") (pintype "passive"))
    )
    (net (code "39") (name "Net-(D7-A)") (class "Default")
      (node (ref "D7") (pin "1") (pinfunction "A_1") (pintype "passive"))
      (node (ref "R8") (pin "1") (pinfunction "1_1") (pintype "passive"))
    )
    (net (code "40") (name "Net-(D8-A)") (class "Default")
      (node (ref "D8") (pin "1") (pinfunction "A_1") (pintype "passive"))
      (node (ref "R9") (pin "1") (pinfunction "1_1") (pintype "passive"))
    )
    (net (code "41") (name "Net-(D9-A)") (class "Default")
      (node (ref "D9") (pin "1") (pinfunction "A_1") (pintype "passive"))
      (node (ref "K1") (pin "5") (pinfunction "T2_5") (pintype "passive"))
      (node (ref "Q3") (pin "1") (pinfunction "C_1") (pintype "passive"))
    )
    (net (code "42") (name "Net-(D10-A)") (class "Default")
      (node (ref "D10") (pin "1") (pinfunction "A_1") (pintype "passive"))
      (node (ref "U2") (pin "3") (pinfunction "INPUT_3") (pintype "passive"))
    )
    (net (code "43") (name "Net-(D10-K)") (class "Default")
      (node (ref "D10") (pin "2") (pinfunction "K_2") (pintype "passive"))
      (node (ref "R34") (pin "2") (pinfunction "2_2") (pintype "passive"))
    )
    (net (code "44") (name "Net-(K1-COM)") (class "Default")
      (node (ref "K1") (pin "1") (pinfunction "COM_1") (pintype "passive"))
      (node (ref "P2") (pin "2") (pinfunction "2_2") (pintype "passive"))
    )
    (net (code "45") (name "Net-(Q1-B)") (class "Default")
      (node (ref "Q1") (pin "2") (pinfunction "B_2") (pintype "passive"))
      (node (ref "R15") (pin "2") (pinfunction "2_2") (pintype "passive"))
    )
    (net (code "46") (name "Net-(Q1-C)") (class "Default")
      (node (ref "P5") (pin "1") (pinfunction "1_1") (pintype "passive"))
      (node (ref "Q1") (pin "1") (pinfunction "C_1") (pintype "passive"))
      (node (ref "Q4") (pin "1") (pinfunction "C_1") (pintype "passive"))
    )
    (net (code "47") (name "Net-(Q1-E)") (class "Default")
      (node (ref "C4") (pin "2") (pinfunction "2_2") (pintype "passive"))
      (node (ref "Q1") (pin "3") (pinfunction "E_3") (pintype "passive"))
      (node (ref "R12") (pin "1") (pinfunction "1_1") (pintype "passive"))
    )
    (net (code "48") (name "Net-(Q2-B)") (class "Default")
      (node (ref "Q2") (pin "2") (pinfunction "B_2") (pintype "passive"))
      (node (ref "R16") (pin "2") (pinfunction "2_2") (pintype "passive"))
    )
    (net (code "49") (name "Net-(Q2-C)") (class "Default")
      (node (ref "Q2") (pin "1") (pinfunction "C_1") (pintype "passive"))
      (node (ref "R15") (pin "1") (pinfunction "1_1") (pintype "passive"))
      (node (ref "R18") (pin "2") (pinfunction "2_2") (pintype "passive"))
    )
    (net (code "50") (name "Net-(Q3-B)") (class "Default")
      (node (ref "Q3") (pin "2") (pinfunction "B_2") (pintype "passive"))
      (node (ref "R19") (pin "1") (pinfunction "1_1") (pintype "passive"))
    )
    (net (code "51") (name "Net-(Q4-B)") (class "Default")
      (node (ref "Q4") (pin "2") (pinfunction "B_2") (pintype "passive"))
      (node (ref "R20") (pin "2") (pinfunction "2_2") (pintype "passive"))
    )
    (net (code "52") (name "Net-(Q5-B)") (class "Default")
      (node (ref "Q5") (pin "2") (pinfunction "B_2") (pintype "passive"))
      (node (ref "R21") (pin "2") (pinfunction "2_2") (pintype "passive"))
    )
    (net (code "53") (name "Net-(Q5-C)") (class "Default")
      (node (ref "Q5") (pin "1") (pinfunction "C_1") (pintype "passive"))
      (node (ref "R20") (pin "1") (pinfunction "1_1") (pintype "passive"))
      (node (ref "R22") (pin "2") (pinfunction "2_2") (pintype "passive"))
    )
    (net (code "54") (name "Net-(Q6-G)") (class "Default")
      (node (ref "Q6") (pin "3") (pinfunction "G_3") (pintype "passive"))
      (node (ref "R26") (pin "1") (pinfunction "1_1") (pintype "passive"))
      (node (ref "T1") (pin "4") (pinfunction "MT1_4") (pintype "passive"))
    )
    (net (code "55") (name "Net-(Q6-M1)") (class "Default")
      (node (ref "C7") (pin "1") (pinfunction "1_1") (pintype "passive"))
      (node (ref "P6") (pin "1") (pinfunction "1_1") (pintype "passive"))
      (node (ref "Q6") (pin "1") (pinfunction "M1_1") (pintype "passive"))
      (node (ref "R26") (pin "2") (pinfunction "2_2") (pintype "passive"))
    )
    (net (code "56") (name "Net-(Q7-B)") (class "Default")
      (node (ref "Q7") (pin "2") (pinfunction "B_2") (pintype "passive"))
      (node (ref "R27") (pin "1") (pinfunction "1_1") (pintype "passive"))
    )
    (net (code "57") (name "Net-(Q7-C)") (class "Default")
      (node (ref "Q7") (pin "1") (pinfunction "C_1") (pintype "passive"))
      (node (ref "R25") (pin "1") (pinfunction "1_1") (pintype "passive"))
    )
    (net (code "58") (name "Net-(R13-Pad2)") (class "Default")
      (node (ref "R13") (pin "2") (pinfunction "2_2") (pintype "passive"))
      (node (ref "R14") (pin "1") (pinfunction "1_1") (pintype "passive"))
    )
    (net (code "59") (name "Net-(R17-TOP)") (class "Default")
      (node (ref "P3") (pin "3") (pinfunction "3_3") (pintype "passive"))
      (node (ref "R14") (pin "2") (pinfunction "2_2") (pintype "passive"))
      (node (ref "R17") (pin "1") (pinfunction "TOP_1") (pintype "passive"))
    )
    (net (code "60") (name "Net-(T1-C)") (class "Default")
      (node (ref "R25") (pin "2") (pinfunction "2_2") (pintype "passive"))
      (node (ref "T1") (pin "2") (pinfunction "C_2") (pintype "passive"))
    )
    (net (code "61") (name "Net-(T1-MT2)") (class "Default")
      (node (ref "R23") (pin "2") (pinfunction "2_2") (pintype "passive"))
      (node (ref "T1") (pin "6") (pinfunction "MT2_6") (pintype "passive"))
    )
    (net (code "62") (name "Net-(U1-EN)") (class "Default")
      (node (ref "C2") (pin "2") (pinfunction "2_2") (pintype "passive"))
      (node (ref "R2") (pin "2") (pinfunction "2_2") (pintype "passive"))
      (node (ref "U1") (pin "3") (pinfunction "EN_3") (pintype "passive"))
    )
    (net (code "63") (name "Net-(U1-GPIO0)") (class "Default")
      (node (ref "S7") (pin "1") (pinfunction "1_1") (pintype "passive"))
      (node (ref "U1") (pin "25") (pinfunction "GPIO0_25") (pintype "passive"))
    )
    (net (code "64") (name "Net-(U3-CLKOUT)") (class "Default")
      (node (ref "R3") (pin "1") (pinfunction "1_1") (pintype "passive"))
      (node (ref "U3") (pin "7") (pinfunction "CLKOUT_7") (pintype "passive"))
    )
    (net (code "65") (name "Net-(U3-OSCI)") (class "Default")
      (node (ref "U3") (pin "1") (pinfunction "OSCI_1") (pintype "passive"))
      (node (ref "Y1") (pin "2") (pinfunction "OSC2_2") (pintype "passive"))
    )
    (net (code "66") (name "Net-(U3-OSCO)") (class "Default")
      (node (ref "U3") (pin "2") (pinfunction "OSCO_2") (pintype "passive"))
      (node (ref "Y1") (pin "1") (pinfunction "OSC1_1") (pintype "passive"))
    )
    (net (code "67") (name "Net-(U3-~{INT})") (class "Default")
      (node (ref "R1") (pin "1") (pinfunction "1_1") (pintype "passive"))
      (node (ref "U3") (pin "3") (pinfunction "~{INT}_3") (pintype "passive"))
    )
    (net (code "68") (name "unconnected-(P4-Pad9)") (class "Default")
      (node (ref "P4") (pin "9") (pinfunction "9_9") (pintype "passive+no_connect"))
    )
    (net (code "69") (name "unconnected-(U1-NC-Pad17)") (class "Default")
      (node (ref "U1") (pin "17") (pinfunction "NC_17") (pintype "passive"))
    )
    (net (code "70") (name "unconnected-(U1-NC-Pad18)") (class "Default")
      (node (ref "U1") (pin "18") (pinfunction "NC_18") (pintype "passive"))
    )
    (net (code "71") (name "unconnected-(U1-NC-Pad19)") (class "Default")
      (node (ref "U1") (pin "19") (pinfunction "NC_19") (pintype "passive"))
    )
    (net (code "72") (name "unconnected-(U1-NC-Pad20)") (class "Default")
      (node (ref "U1") (pin "20") (pinfunction "NC_20") (pintype "passive"))
    )
    (net (code "73") (name "unconnected-(U1-NC-Pad21)") (class "Default")
      (node (ref "U1") (pin "21") (pinfunction "NC_21") (pintype "passive"))
    )
    (net (code "74") (name "unconnected-(U1-NC-Pad22)") (class "Default")
      (node (ref "U1") (pin "22") (pinfunction "NC_22") (pintype "passive"))
    )
    (net (code "75") (name "unconnected-(U1-NC-Pad32)") (class "Default")
      (node (ref "U1") (pin "32") (pinfunction "NC_32") (pintype "passive"))
    )
    (net (code "76") (name "unconnected-(U1-SENSOR_VN-Pad5)") (class "Default")
      (node (ref "U1") (pin "5") (pinfunction "SENSOR_VN_5") (pintype "passive"))
    )
    (net (code "77") (name "unconnected-(U1-SENSOR_VP-Pad4)") (class "Default")
      (node (ref "U1") (pin "4") (pinfunction "SENSOR_VP_4") (pintype "passive"))
    )
    (net (code "78") (name "unconnected-(U2-OUTPUT-Pad2)") (class "Default")
      (node (ref "U2") (pin "2") (pinfunction "OUTPUT_2") (pintype "passive+no_connect"))
    )
  )
)
